# Adafruit_ESP32-S3_Reverse_TFT.net
KiCad netlist of a schematic drawn in EAGLE
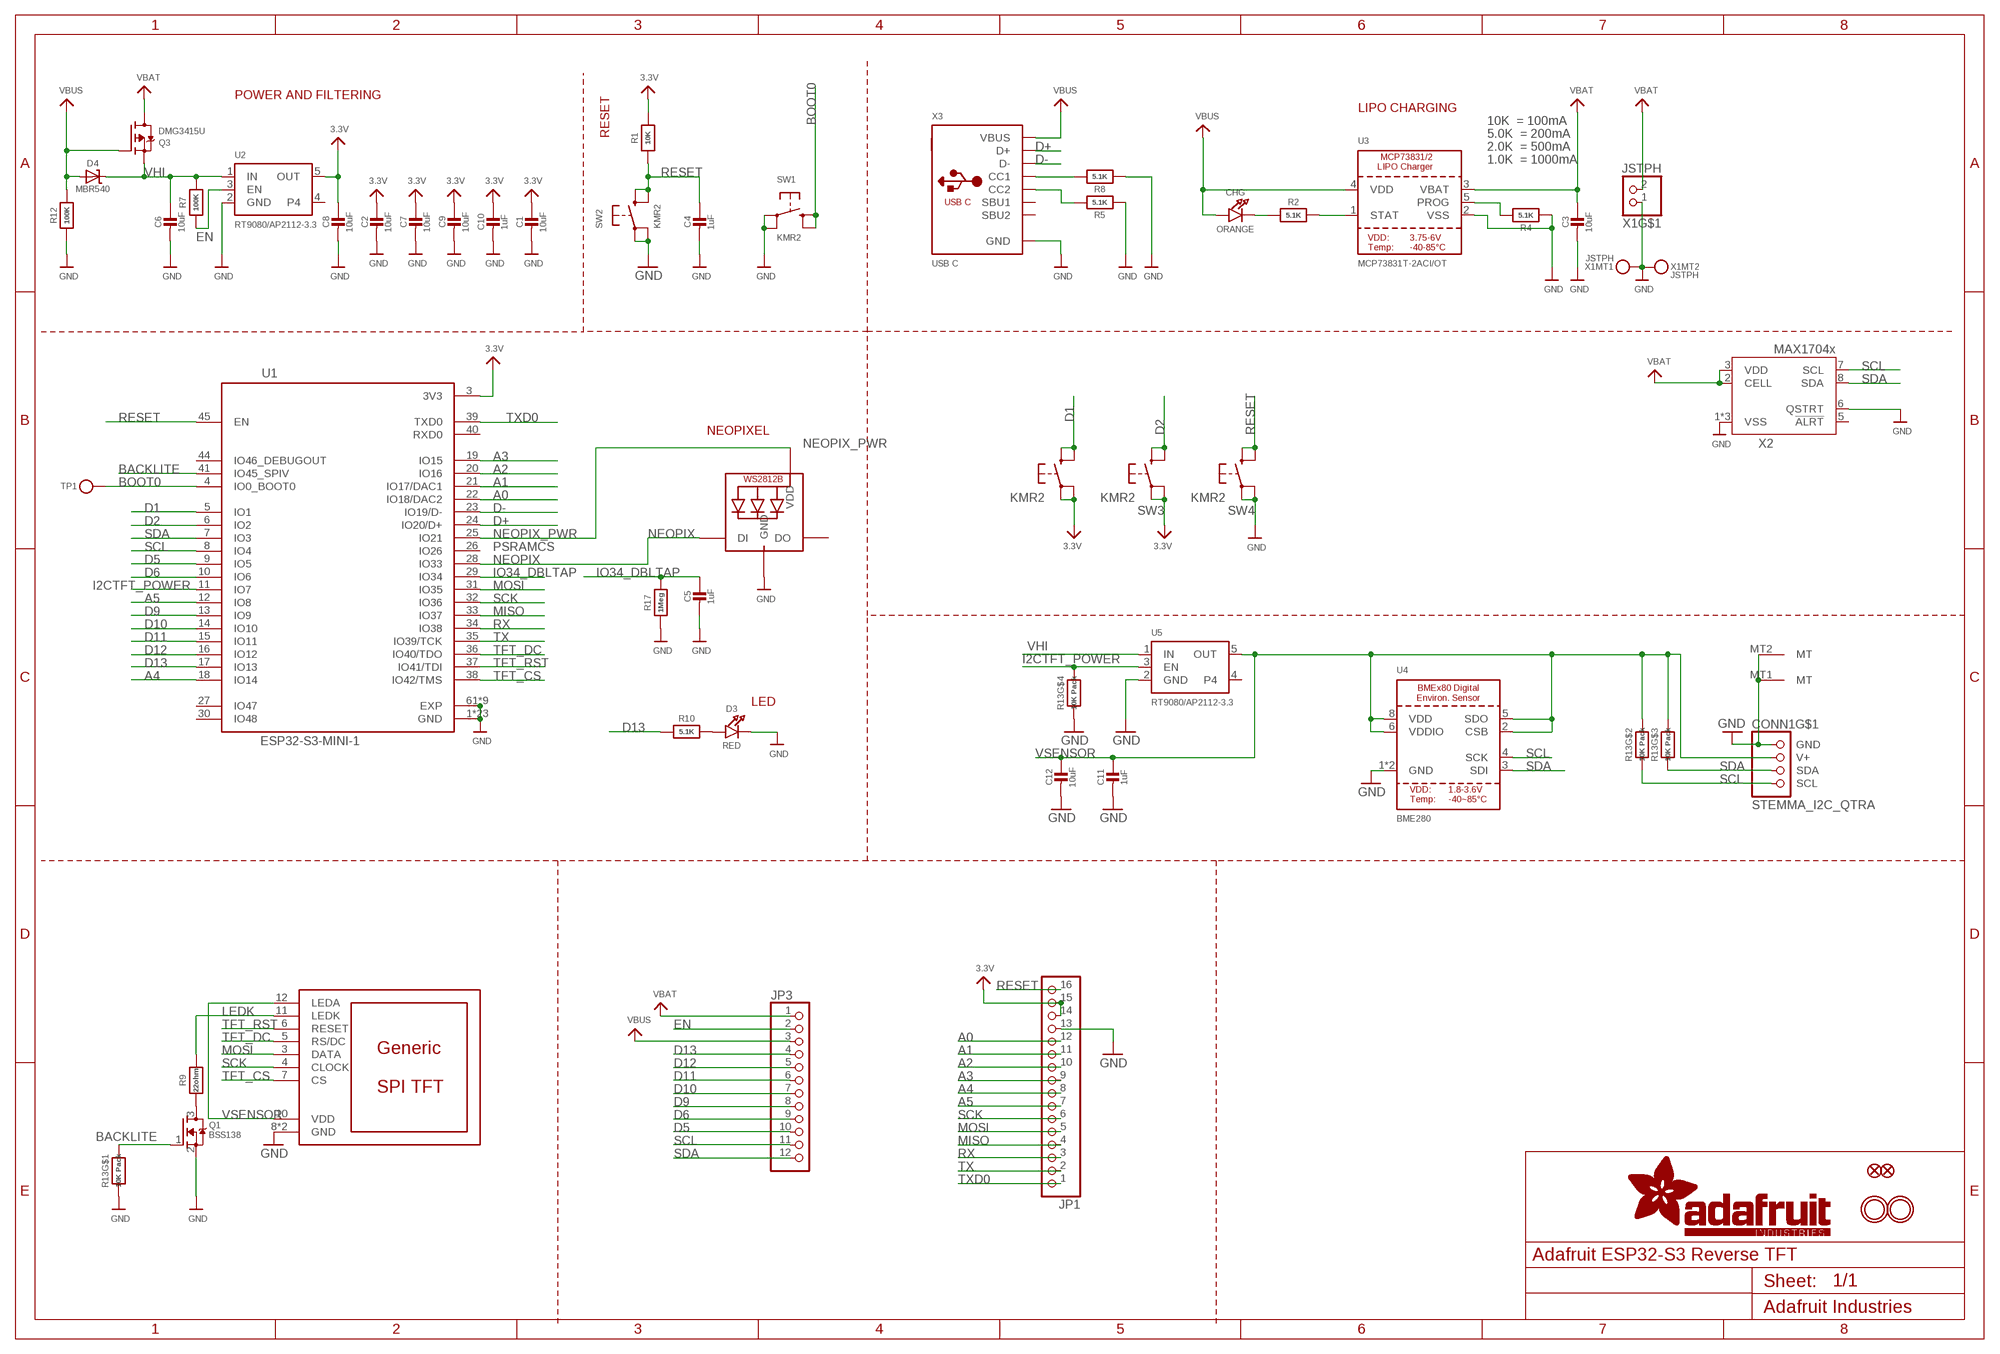
[diagram p0: schematic, sheet 1]

(export (version "E")
  (design (tool "Eeschema 10.0.6"))
  (components
    (comp (ref "C1")
      (value "10uF")
      (footprint "eagle-import:0805-NO")
      (libsource (lib "eagle-import") (part "CAP_CERAMIC0805-NOOUTLINE"))
    )
    (comp (ref "C2")
      (value "10uF")
      (footprint "eagle-import:0805-NO")
      (libsource (lib "eagle-import") (part "CAP_CERAMIC0805-NOOUTLINE"))
    )
    (comp (ref "C3")
      (value "10uF")
      (footprint "eagle-import:0805-NO")
      (libsource (lib "eagle-import") (part "CAP_CERAMIC0805-NOOUTLINE"))
    )
    (comp (ref "C4")
      (value "1uF")
      (footprint "eagle-import:0603-NO")
      (libsource (lib "eagle-import") (part "CAP_CERAMIC0603_NO"))
    )
    (comp (ref "C5")
      (value "1uF")
      (footprint "eagle-import:0603-NO")
      (libsource (lib "eagle-import") (part "CAP_CERAMIC0603_NO"))
    )
    (comp (ref "C6")
      (value "10uF")
      (footprint "eagle-import:0805-NO")
      (libsource (lib "eagle-import") (part "CAP_CERAMIC0805-NOOUTLINE"))
    )
    (comp (ref "C7")
      (value "10uF")
      (footprint "eagle-import:0805-NO")
      (libsource (lib "eagle-import") (part "CAP_CERAMIC0805-NOOUTLINE"))
    )
    (comp (ref "C8")
      (value "10uF")
      (footprint "eagle-import:0805-NO")
      (libsource (lib "eagle-import") (part "CAP_CERAMIC0805-NOOUTLINE"))
    )
    (comp (ref "C9")
      (value "10uF")
      (footprint "eagle-import:0805-NO")
      (libsource (lib "eagle-import") (part "CAP_CERAMIC0805-NOOUTLINE"))
    )
    (comp (ref "C10")
      (value "1uF")
      (footprint "eagle-import:0603-NO")
      (libsource (lib "eagle-import") (part "CAP_CERAMIC0603_NO"))
    )
    (comp (ref "C11")
      (value "1uF")
      (footprint "eagle-import:0603-NO")
      (libsource (lib "eagle-import") (part "CAP_CERAMIC0603_NO"))
    )
    (comp (ref "C12")
      (value "10uF")
      (footprint "eagle-import:0805-NO")
      (libsource (lib "eagle-import") (part "CAP_CERAMIC0805-NOOUTLINE"))
    )
    (comp (ref "CHG")
      (value "ORANGE")
      (footprint "eagle-import:CHIPLED_0603_NOOUTLINE")
      (libsource (lib "eagle-import") (part "LED0603_NOOUTLINE"))
    )
    (comp (ref "CONN1")
      (value "STEMMA_I2C_QTRA")
      (footprint "eagle-import:JST_SH4_RA")
      (libsource (lib "eagle-import") (part "STEMMA_I2C_QTRA"))
    )
    (comp (ref "D3")
      (value "RED")
      (footprint "eagle-import:CHIPLED_0603_NOOUTLINE")
      (libsource (lib "eagle-import") (part "LED0603_NOOUTLINE"))
    )
    (comp (ref "D4")
      (value "MBR540")
      (footprint "eagle-import:SOD-123")
      (libsource (lib "eagle-import") (part "DIODE-SCHOTTKYSOD-123"))
    )
    (comp (ref "DISP1")
      (value "DISP_LCD_GENERIC_SPI_1.14IN_240X135_WRAPUNDER")
      (footprint "eagle-import:TFT_1.14IN_240X135_WRAPUNDER")
      (libsource (lib "eagle-import") (part "DISP_LCD_GENERIC_SPI_1.14IN_240X135_WRAPUNDER"))
    )
    (comp (ref "JP1")
      (value "HEADER-1X16_MIN")
      (footprint "eagle-import:1X16_ROUND_MIN")
      (libsource (lib "eagle-import") (part "HEADER-1X16_MIN"))
    )
    (comp (ref "JP3")
      (value "HEADER-1X12_MIN")
      (footprint "eagle-import:1X12_ROUND_MIN")
      (libsource (lib "eagle-import") (part "HEADER-1X12_MIN"))
    )
    (comp (ref "LED1")
      (value "WS2812B_SK6805_1515")
      (footprint "eagle-import:SK6805_1515")
      (libsource (lib "eagle-import") (part "WS2812B_SK6805_1515"))
    )
    (comp (ref "Q1")
      (value "BSS138")
      (footprint "eagle-import:SC70")
      (libsource (lib "eagle-import") (part "MOSFET-N_SC70"))
    )
    (comp (ref "Q3")
      (value "DMG3415U")
      (footprint "eagle-import:SOT23-R")
      (libsource (lib "eagle-import") (part "MOSFET-P"))
    )
    (comp (ref "R1")
      (value "10K")
      (footprint "eagle-import:0603-NO")
      (libsource (lib "eagle-import") (part "RESISTOR_0603_NOOUT"))
    )
    (comp (ref "R2")
      (value "5.1K")
      (footprint "eagle-import:0603-NO")
      (libsource (lib "eagle-import") (part "RESISTOR_0603_NOOUT"))
    )
    (comp (ref "R4")
      (value "5.1K")
      (footprint "eagle-import:0603-NO")
      (libsource (lib "eagle-import") (part "RESISTOR_0603_NOOUT"))
    )
    (comp (ref "R5")
      (value "5.1K")
      (footprint "eagle-import:0603-NO")
      (libsource (lib "eagle-import") (part "RESISTOR_0603_NOOUT"))
    )
    (comp (ref "R7")
      (value "100K")
      (footprint "eagle-import:0603-NO")
      (libsource (lib "eagle-import") (part "RESISTOR_0603_NOOUT"))
    )
    (comp (ref "R8")
      (value "5.1K")
      (footprint "eagle-import:0603-NO")
      (libsource (lib "eagle-import") (part "RESISTOR_0603_NOOUT"))
    )
    (comp (ref "R9")
      (value "22ohm")
      (footprint "eagle-import:0603-NO")
      (libsource (lib "eagle-import") (part "RESISTOR_0603_NOOUT"))
    )
    (comp (ref "R10")
      (value "5.1K")
      (footprint "eagle-import:0603-NO")
      (libsource (lib "eagle-import") (part "RESISTOR_0603_NOOUT"))
    )
    (comp (ref "R12")
      (value "100K")
      (footprint "eagle-import:0603-NO")
      (libsource (lib "eagle-import") (part "RESISTOR_0603_NOOUT"))
    )
    (comp (ref "R13")
      (value "10K Pack")
      (footprint "eagle-import:RESPACK_4X0603")
      (libsource (lib "eagle-import") (part "RESISTOR_4PACK"))
    )
    (comp (ref "R17")
      (value "1Meg")
      (footprint "eagle-import:0603-NO")
      (libsource (lib "eagle-import") (part "RESISTOR_0603_NOOUT"))
    )
    (comp (ref "SW1")
      (value "KMR2")
      (footprint "eagle-import:BTN_RKB2_4.6X2.8")
      (libsource (lib "eagle-import") (part "SWITCH_TACT_SMT_RKB2"))
    )
    (comp (ref "SW2")
      (value "KMR2")
      (footprint "eagle-import:BTN_RKB2_4.6X2.8")
      (libsource (lib "eagle-import") (part "SWITCH_TACT_SMT_RKB2"))
    )
    (comp (ref "SW3")
      (value "KMR2")
      (footprint "eagle-import:BTN_RKB2_4.6X2.8")
      (libsource (lib "eagle-import") (part "SWITCH_TACT_SMT_RKB2"))
    )
    (comp (ref "SW4")
      (value "KMR2")
      (footprint "eagle-import:BTN_RKB2_4.6X2.8")
      (libsource (lib "eagle-import") (part "SWITCH_TACT_SMT_RKB2"))
    )
    (comp (ref "SW5")
      (value "KMR2")
      (footprint "eagle-import:BTN_RKB2_4.6X2.8")
      (libsource (lib "eagle-import") (part "SWITCH_TACT_SMT_RKB2"))
    )
    (comp (ref "TP1")
      (value "TESTPOINTROUND1.5MMNO")
      (footprint "eagle-import:TESTPOINT_ROUND_1.5MM_NO")
      (libsource (lib "eagle-import") (part "TESTPOINTROUND1.5MMNO"))
    )
    (comp (ref "U$31")
      (value "MOUNTINGHOLE2.5")
      (footprint "eagle-import:MOUNTINGHOLE_2.5_PLATED")
      (libsource (lib "eagle-import") (part "MOUNTINGHOLE2.5"))
    )
    (comp (ref "U$32")
      (value "MOUNTINGHOLE2.5")
      (footprint "eagle-import:MOUNTINGHOLE_2.5_PLATED")
      (libsource (lib "eagle-import") (part "MOUNTINGHOLE2.5"))
    )
    (comp (ref "U$34")
      (value "FIDUCIAL_1MM")
      (footprint "eagle-import:FIDUCIAL_1MM")
      (libsource (lib "eagle-import") (part "FIDUCIAL_1MM"))
    )
    (comp (ref "U$35")
      (value "FIDUCIAL_1MM")
      (footprint "eagle-import:FIDUCIAL_1MM")
      (libsource (lib "eagle-import") (part "FIDUCIAL_1MM"))
    )
    (comp (ref "U1")
      (value "ESP32-S3-MINI-1")
      (footprint "eagle-import:ESP32-S2-MINI-1")
      (fields
        (field (name "MANUFACTURER_PART_NUMBER") "ESP32-S2-MINI-1")
        (field (name "COPYRIGHT") "Copyright (C) 2018 Accelerated Designs. All rights reserved")
      )
      (libsource (lib "eagle-import") (part "ESP32-S3-MINI-1"))
    )
    (comp (ref "U2")
      (value "RT9080/AP2112-3.3")
      (footprint "eagle-import:SOT23-5")
      (fields (field (name "JLC_ROTATION") "0"))
      (libsource (lib "eagle-import") (part "VREG_SOT23-5"))
    )
    (comp (ref "U3")
      (value "MCP73831T-2ACI/OT")
      (footprint "eagle-import:SOT23-5")
      (libsource (lib "eagle-import") (part "MCP73831/2"))
    )
    (comp (ref "U4")
      (value "BME280")
      (footprint "eagle-import:BME280")
      (libsource (lib "eagle-import") (part "BME280"))
    )
    (comp (ref "U5")
      (value "RT9080/AP2112-3.3")
      (footprint "eagle-import:SOT23-5")
      (fields (field (name "JLC_ROTATION") "0"))
      (libsource (lib "eagle-import") (part "VREG_SOT23-5"))
    )
    (comp (ref "X1")
      (value "JSTPH")
      (footprint "eagle-import:JSTPH2_BATT")
      (libsource (lib "eagle-import") (part "CON_JST_PH_2PIN_MT_BATT"))
    )
    (comp (ref "X2")
      (value "MAX17048/T")
      (footprint "eagle-import:TDFN8_2X2MM")
      (libsource (lib "eagle-import") (part "MAX17048/T"))
    )
    (comp (ref "X3")
      (value "USB C")
      (footprint "eagle-import:USB_C_CUSB31-CFM2AX-01-X")
      (libsource (lib "eagle-import") (part "USB_C"))
    )
  )
  (nets
    (net (code "1") (name "/A0") (class "Default")
      (node (ref "JP1") (pin "12") (pinfunction "12_12") (pintype "passive"))
      (node (ref "U1") (pin "22") (pinfunction "IO18/DAC2_22") (pintype "bidirectional"))
    )
    (net (code "2") (name "/A1") (class "Default")
      (node (ref "JP1") (pin "11") (pinfunction "11_11") (pintype "passive"))
      (node (ref "U1") (pin "21") (pinfunction "IO17/DAC1_21") (pintype "bidirectional"))
    )
    (net (code "3") (name "/A2") (class "Default")
      (node (ref "JP1") (pin "10") (pinfunction "10_10") (pintype "passive"))
      (node (ref "U1") (pin "20") (pinfunction "IO16_20") (pintype "bidirectional"))
    )
    (net (code "4") (name "/A3") (class "Default")
      (node (ref "JP1") (pin "9") (pinfunction "9_9") (pintype "passive"))
      (node (ref "U1") (pin "19") (pinfunction "IO15_19") (pintype "bidirectional"))
    )
    (net (code "5") (name "/A4") (class "Default")
      (node (ref "JP1") (pin "8") (pinfunction "8_8") (pintype "passive"))
      (node (ref "U1") (pin "18") (pinfunction "IO14_18") (pintype "bidirectional"))
    )
    (net (code "6") (name "/A5") (class "Default")
      (node (ref "JP1") (pin "7") (pinfunction "7_7") (pintype "passive"))
      (node (ref "U1") (pin "12") (pinfunction "IO8_12") (pintype "bidirectional"))
    )
    (net (code "7") (name "/BACKLITE") (class "Default")
      (node (ref "Q1") (pin "1") (pinfunction "G_1") (pintype "bidirectional"))
      (node (ref "R13") (pin "8") (pinfunction "2_8") (pintype "passive"))
      (node (ref "U1") (pin "41") (pinfunction "IO45_SPIV_41") (pintype "bidirectional"))
    )
    (net (code "8") (name "/BOOT0") (class "Default")
      (node (ref "SW1") (pin "B") (pinfunction "S_B") (pintype "passive"))
      (node (ref "SW1") (pin "B'") (pinfunction "S1_B'") (pintype "passive"))
      (node (ref "TP1") (pin "P$1") (pinfunction "P$1_P$1") (pintype "bidirectional"))
      (node (ref "U1") (pin "4") (pinfunction "IO0_BOOT0_4") (pintype "bidirectional"))
    )
    (net (code "9") (name "/D+") (class "Default")
      (node (ref "U1") (pin "24") (pinfunction "IO20/D+_24") (pintype "bidirectional"))
      (node (ref "X3") (pin "A6") (pinfunction "D+_A6") (pintype "bidirectional"))
      (node (ref "X3") (pin "B6") (pinfunction "D+_B6") (pintype "bidirectional"))
    )
    (net (code "10") (name "/D-") (class "Default")
      (node (ref "U1") (pin "23") (pinfunction "IO19/D-_23") (pintype "bidirectional"))
      (node (ref "X3") (pin "A7") (pinfunction "D-_A7") (pintype "bidirectional"))
      (node (ref "X3") (pin "B7") (pinfunction "D-_B7") (pintype "bidirectional"))
    )
    (net (code "11") (name "/D1") (class "Default")
      (node (ref "SW5") (pin "B") (pinfunction "S_B") (pintype "passive"))
      (node (ref "SW5") (pin "B'") (pinfunction "S1_B'") (pintype "passive"))
      (node (ref "U1") (pin "5") (pinfunction "IO1_5") (pintype "bidirectional"))
    )
    (net (code "12") (name "/D2") (class "Default")
      (node (ref "SW3") (pin "B") (pinfunction "S_B") (pintype "passive"))
      (node (ref "SW3") (pin "B'") (pinfunction "S1_B'") (pintype "passive"))
      (node (ref "U1") (pin "6") (pinfunction "IO2_6") (pintype "bidirectional"))
    )
    (net (code "13") (name "/D5") (class "Default")
      (node (ref "JP3") (pin "10") (pinfunction "10_10") (pintype "passive"))
      (node (ref "U1") (pin "9") (pinfunction "IO5_9") (pintype "bidirectional"))
    )
    (net (code "14") (name "/D6") (class "Default")
      (node (ref "JP3") (pin "9") (pinfunction "9_9") (pintype "passive"))
      (node (ref "U1") (pin "10") (pinfunction "IO6_10") (pintype "bidirectional"))
    )
    (net (code "15") (name "/D9") (class "Default")
      (node (ref "JP3") (pin "8") (pinfunction "8_8") (pintype "passive"))
      (node (ref "U1") (pin "13") (pinfunction "IO9_13") (pintype "bidirectional"))
    )
    (net (code "16") (name "/D10") (class "Default")
      (node (ref "JP3") (pin "7") (pinfunction "7_7") (pintype "passive"))
      (node (ref "U1") (pin "14") (pinfunction "IO10_14") (pintype "bidirectional"))
    )
    (net (code "17") (name "/D11") (class "Default")
      (node (ref "JP3") (pin "6") (pinfunction "6_6") (pintype "passive"))
      (node (ref "U1") (pin "15") (pinfunction "IO11_15") (pintype "bidirectional"))
    )
    (net (code "18") (name "/D12") (class "Default")
      (node (ref "JP3") (pin "5") (pinfunction "5_5") (pintype "passive"))
      (node (ref "U1") (pin "16") (pinfunction "IO12_16") (pintype "bidirectional"))
    )
    (net (code "19") (name "/D13") (class "Default")
      (node (ref "JP3") (pin "4") (pinfunction "4_4") (pintype "passive"))
      (node (ref "R10") (pin "1") (pinfunction "1_1") (pintype "passive"))
      (node (ref "U1") (pin "17") (pinfunction "IO13_17") (pintype "bidirectional"))
    )
    (net (code "20") (name "/EN") (class "Default")
      (node (ref "JP3") (pin "2") (pinfunction "2_2") (pintype "passive"))
      (node (ref "R7") (pin "1") (pinfunction "1_1") (pintype "passive"))
      (node (ref "U2") (pin "3") (pinfunction "EN_3") (pintype "input"))
    )
    (net (code "21") (name "/I2CTFT_POWER") (class "Default")
      (node (ref "R13") (pin "5") (pinfunction "2_5") (pintype "passive"))
      (node (ref "U1") (pin "11") (pinfunction "IO7_11") (pintype "bidirectional"))
      (node (ref "U5") (pin "3") (pinfunction "EN_3") (pintype "input"))
    )
    (net (code "22") (name "/IO34_DBLTAP") (class "Default")
      (node (ref "C5") (pin "1") (pinfunction "1_1") (pintype "passive"))
      (node (ref "R17") (pin "2") (pinfunction "2_2") (pintype "passive"))
      (node (ref "U1") (pin "29") (pinfunction "IO34_29") (pintype "input"))
    )
    (net (code "23") (name "/LEDK") (class "Default")
      (node (ref "DISP1") (pin "11") (pinfunction "LEDK_11") (pintype "input"))
      (node (ref "R9") (pin "2") (pinfunction "2_2") (pintype "passive"))
    )
    (net (code "24") (name "/MISO") (class "Default")
      (node (ref "JP1") (pin "4") (pinfunction "4_4") (pintype "passive"))
      (node (ref "U1") (pin "33") (pinfunction "IO37_33") (pintype "bidirectional"))
    )
    (net (code "25") (name "/MOSI") (class "Default")
      (node (ref "DISP1") (pin "3") (pinfunction "DATA_3") (pintype "bidirectional"))
      (node (ref "JP1") (pin "5") (pinfunction "5_5") (pintype "passive"))
      (node (ref "U1") (pin "31") (pinfunction "IO35_31") (pintype "input"))
    )
    (net (code "26") (name "/NEOPIX") (class "Default")
      (node (ref "LED1") (pin "1") (pinfunction "DI_1") (pintype "input"))
      (node (ref "U1") (pin "28") (pinfunction "IO33_28") (pintype "bidirectional"))
    )
    (net (code "27") (name "/NEOPIX_PWR") (class "Default")
      (node (ref "LED1") (pin "2") (pinfunction "VDD_2") (pintype "power_in"))
      (node (ref "U1") (pin "25") (pinfunction "IO21_25") (pintype "bidirectional"))
    )
    (net (code "28") (name "/RESET") (class "Default")
      (node (ref "C4") (pin "1") (pinfunction "1_1") (pintype "passive"))
      (node (ref "JP1") (pin "16") (pinfunction "16_16") (pintype "passive"))
      (node (ref "R1") (pin "1") (pinfunction "1_1") (pintype "passive"))
      (node (ref "SW2") (pin "B") (pinfunction "S_B") (pintype "passive"))
      (node (ref "SW2") (pin "B'") (pinfunction "S1_B'") (pintype "passive"))
      (node (ref "SW4") (pin "B") (pinfunction "S_B") (pintype "passive"))
      (node (ref "SW4") (pin "B'") (pinfunction "S1_B'") (pintype "passive"))
      (node (ref "U1") (pin "45") (pinfunction "EN_45") (pintype "input"))
    )
    (net (code "29") (name "/RX") (class "Default")
      (node (ref "JP1") (pin "3") (pinfunction "3_3") (pintype "passive"))
      (node (ref "U1") (pin "34") (pinfunction "IO38_34") (pintype "bidirectional"))
    )
    (net (code "30") (name "/SCK") (class "Default")
      (node (ref "DISP1") (pin "4") (pinfunction "CLOCK_4") (pintype "input"))
      (node (ref "JP1") (pin "6") (pinfunction "6_6") (pintype "passive"))
      (node (ref "U1") (pin "32") (pinfunction "IO36_32") (pintype "bidirectional"))
    )
    (net (code "31") (name "/SCL") (class "Default")
      (node (ref "CONN1") (pin "4") (pinfunction "SCL_4") (pintype "passive"))
      (node (ref "JP3") (pin "11") (pinfunction "11_11") (pintype "passive"))
      (node (ref "R13") (pin "2") (pinfunction "1_2") (pintype "passive"))
      (node (ref "U1") (pin "8") (pinfunction "IO4_8") (pintype "bidirectional"))
      (node (ref "U4") (pin "4") (pinfunction "SCK_4") (pintype "input"))
      (node (ref "X2") (pin "7") (pinfunction "SCL_7") (pintype "bidirectional"))
    )
    (net (code "32") (name "/SDA") (class "Default")
      (node (ref "CONN1") (pin "3") (pinfunction "SDA_3") (pintype "passive"))
      (node (ref "JP3") (pin "12") (pinfunction "12_12") (pintype "passive"))
      (node (ref "R13") (pin "3") (pinfunction "1_3") (pintype "passive"))
      (node (ref "U1") (pin "7") (pinfunction "IO3_7") (pintype "bidirectional"))
      (node (ref "U4") (pin "3") (pinfunction "SDI_3") (pintype "input"))
      (node (ref "X2") (pin "8") (pinfunction "SDA_8") (pintype "bidirectional"))
    )
    (net (code "33") (name "/TFT_CS") (class "Default")
      (node (ref "DISP1") (pin "7") (pinfunction "CS_7") (pintype "input"))
      (node (ref "U1") (pin "38") (pinfunction "IO42/TMS_38") (pintype "bidirectional"))
    )
    (net (code "34") (name "/TFT_DC") (class "Default")
      (node (ref "DISP1") (pin "5") (pinfunction "RS/DC_5") (pintype "input"))
      (node (ref "U1") (pin "36") (pinfunction "IO40/TDO_36") (pintype "bidirectional"))
    )
    (net (code "35") (name "/TFT_RST") (class "Default")
      (node (ref "DISP1") (pin "6") (pinfunction "RESET_6") (pintype "input"))
      (node (ref "U1") (pin "37") (pinfunction "IO41/TDI_37") (pintype "bidirectional"))
    )
    (net (code "36") (name "/TX") (class "Default")
      (node (ref "JP1") (pin "2") (pinfunction "2_2") (pintype "passive"))
      (node (ref "U1") (pin "35") (pinfunction "IO39/TCK_35") (pintype "bidirectional"))
    )
    (net (code "37") (name "/TXD0") (class "Default")
      (node (ref "JP1") (pin "1") (pinfunction "1_1") (pintype "passive"))
      (node (ref "U1") (pin "39") (pinfunction "TXD0_39") (pintype "bidirectional"))
    )
    (net (code "38") (name "/VHI") (class "Default")
      (node (ref "C6") (pin "1") (pinfunction "1_1") (pintype "passive"))
      (node (ref "D4") (pin "C") (pinfunction "C_C") (pintype "passive"))
      (node (ref "Q3") (pin "2") (pinfunction "S_2") (pintype "passive"))
      (node (ref "R7") (pin "2") (pinfunction "2_2") (pintype "passive"))
      (node (ref "U2") (pin "1") (pinfunction "IN_1") (pintype "power_in"))
      (node (ref "U5") (pin "1") (pinfunction "IN_1") (pintype "power_in"))
    )
    (net (code "39") (name "/VSENSOR") (class "Default")
      (node (ref "C11") (pin "1") (pinfunction "1_1") (pintype "passive"))
      (node (ref "C12") (pin "1") (pinfunction "1_1") (pintype "passive"))
      (node (ref "CONN1") (pin "2") (pinfunction "V+_2") (pintype "passive"))
      (node (ref "DISP1") (pin "10") (pinfunction "VDD_10") (pintype "power_in"))
      (node (ref "DISP1") (pin "12") (pinfunction "LEDA_12") (pintype "input"))
      (node (ref "R13") (pin "6") (pinfunction "2_6") (pintype "passive"))
      (node (ref "R13") (pin "7") (pinfunction "2_7") (pintype "passive"))
      (node (ref "U4") (pin "2") (pinfunction "CSB_2") (pintype "input"))
      (node (ref "U4") (pin "5") (pinfunction "SDO_5") (pintype "output"))
      (node (ref "U4") (pin "6") (pinfunction "VDDIO_6") (pintype "power_in"))
      (node (ref "U4") (pin "8") (pinfunction "VDD_8") (pintype "power_in"))
      (node (ref "U5") (pin "5") (pinfunction "OUT_5") (pintype "power_in"))
    )
    (net (code "40") (name "3.3V") (class "Default")
      (node (ref "C1") (pin "1") (pinfunction "1_1") (pintype "passive"))
      (node (ref "C10") (pin "1") (pinfunction "1_1") (pintype "passive"))
      (node (ref "C2") (pin "1") (pinfunction "1_1") (pintype "passive"))
      (node (ref "C7") (pin "1") (pinfunction "1_1") (pintype "passive"))
      (node (ref "C8") (pin "1") (pinfunction "1_1") (pintype "passive"))
      (node (ref "C9") (pin "1") (pinfunction "1_1") (pintype "passive"))
      (node (ref "JP1") (pin "14") (pinfunction "14_14") (pintype "passive"))
      (node (ref "JP1") (pin "15") (pinfunction "15_15") (pintype "passive"))
      (node (ref "R1") (pin "2") (pinfunction "2_2") (pintype "passive"))
      (node (ref "SW3") (pin "A") (pinfunction "P_A") (pintype "passive"))
      (node (ref "SW3") (pin "A'") (pinfunction "P1_A'") (pintype "passive"))
      (node (ref "SW5") (pin "A") (pinfunction "P_A") (pintype "passive"))
      (node (ref "SW5") (pin "A'") (pinfunction "P1_A'") (pintype "passive"))
      (node (ref "U1") (pin "3") (pinfunction "3V3_3") (pintype "power_in"))
      (node (ref "U2") (pin "5") (pinfunction "OUT_5") (pintype "power_in"))
    )
    (net (code "41") (name "GND") (class "Default")
      (node (ref "C1") (pin "2") (pinfunction "2_2") (pintype "passive"))
      (node (ref "C10") (pin "2") (pinfunction "2_2") (pintype "passive"))
      (node (ref "C11") (pin "2") (pinfunction "2_2") (pintype "passive"))
      (node (ref "C12") (pin "2") (pinfunction "2_2") (pintype "passive"))
      (node (ref "C2") (pin "2") (pinfunction "2_2") (pintype "passive"))
      (node (ref "C3") (pin "2") (pinfunction "2_2") (pintype "passive"))
      (node (ref "C4") (pin "2") (pinfunction "2_2") (pintype "passive"))
      (node (ref "C5") (pin "2") (pinfunction "2_2") (pintype "passive"))
      (node (ref "C6") (pin "2") (pinfunction "2_2") (pintype "passive"))
      (node (ref "C7") (pin "2") (pinfunction "2_2") (pintype "passive"))
      (node (ref "C8") (pin "2") (pinfunction "2_2") (pintype "passive"))
      (node (ref "C9") (pin "2") (pinfunction "2_2") (pintype "passive"))
      (node (ref "CONN1") (pin "1") (pinfunction "GND_1") (pintype "passive"))
      (node (ref "CONN1") (pin "MT1") (pinfunction "MT_MT1") (pintype "bidirectional"))
      (node (ref "CONN1") (pin "MT2") (pinfunction "MT_MT2") (pintype "bidirectional"))
      (node (ref "D3") (pin "C") (pinfunction "C_C") (pintype "passive"))
      (node (ref "DISP1") (pin "13") (pinfunction "GND_13") (pintype "power_in"))
      (node (ref "DISP1") (pin "8") (pinfunction "GND_8") (pintype "power_in"))
      (node (ref "JP1") (pin "13") (pinfunction "13_13") (pintype "passive"))
      (node (ref "LED1") (pin "4") (pinfunction "GND_4") (pintype "power_in"))
      (node (ref "Q1") (pin "2") (pinfunction "S_2") (pintype "bidirectional"))
      (node (ref "R12") (pin "1") (pinfunction "1_1") (pintype "passive"))
      (node (ref "R13") (pin "1") (pinfunction "1_1") (pintype "passive"))
      (node (ref "R13") (pin "4") (pinfunction "1_4") (pintype "passive"))
      (node (ref "R17") (pin "1") (pinfunction "1_1") (pintype "passive"))
      (node (ref "R4") (pin "1") (pinfunction "1_1") (pintype "passive"))
      (node (ref "R5") (pin "1") (pinfunction "1_1") (pintype "passive"))
      (node (ref "R8") (pin "1") (pinfunction "1_1") (pintype "passive"))
      (node (ref "SW1") (pin "A") (pinfunction "P_A") (pintype "passive"))
      (node (ref "SW1") (pin "A'") (pinfunction "P1_A'") (pintype "passive"))
      (node (ref "SW2") (pin "A") (pinfunction "P_A") (pintype "passive"))
      (node (ref "SW2") (pin "A'") (pinfunction "P1_A'") (pintype "passive"))
      (node (ref "SW4") (pin "A") (pinfunction "P_A") (pintype "passive"))
      (node (ref "SW4") (pin "A'") (pinfunction "P1_A'") (pintype "passive"))
      (node (ref "U1") (pin "1") (pinfunction "GND_1") (pintype "power_in"))
      (node (ref "U1") (pin "2") (pinfunction "GND_2") (pintype "power_in"))
      (node (ref "U1") (pin "42") (pinfunction "GND_42") (pintype "power_in"))
      (node (ref "U1") (pin "43") (pinfunction "GND_43") (pintype "power_in"))
      (node (ref "U1") (pin "46") (pinfunction "GND_46") (pintype "power_in"))
      (node (ref "U1") (pin "47") (pinfunction "GND_47") (pintype "power_in"))
      (node (ref "U1") (pin "48") (pinfunction "GND_48") (pintype "power_in"))
      (node (ref "U1") (pin "49") (pinfunction "GND_49") (pintype "power_in"))
      (node (ref "U1") (pin "50") (pinfunction "GND_50") (pintype "power_in"))
      (node (ref "U1") (pin "51") (pinfunction "GND_51") (pintype "power_in"))
      (node (ref "U1") (pin "52") (pinfunction "GND_52") (pintype "power_in"))
      (node (ref "U1") (pin "53") (pinfunction "GND_53") (pintype "power_in"))
      (node (ref "U1") (pin "54") (pinfunction "GND_54") (pintype "power_in"))
      (node (ref "U1") (pin "55") (pinfunction "GND_55") (pintype "power_in"))
      (node (ref "U1") (pin "56") (pinfunction "GND_56") (pintype "power_in"))
      (node (ref "U1") (pin "57") (pinfunction "GND_57") (pintype "power_in"))
      (node (ref "U1") (pin "58") (pinfunction "GND_58") (pintype "power_in"))
      (node (ref "U1") (pin "59") (pinfunction "GND_59") (pintype "power_in"))
      (node (ref "U1") (pin "60") (pinfunction "GND_60") (pintype "power_in"))
      (node (ref "U1") (pin "61") (pinfunction "EXP_61") (pintype "power_in"))
      (node (ref "U1") (pin "62") (pinfunction "GND_62") (pintype "power_in"))
      (node (ref "U1") (pin "63") (pinfunction "GND_63") (pintype "power_in"))
      (node (ref "U1") (pin "64") (pinfunction "GND_64") (pintype "power_in"))
      (node (ref "U1") (pin "65") (pinfunction "GND_65") (pintype "power_in"))
      (node (ref "U1") (pin "66") (pinfunction "EXP_66") (pintype "power_in"))
      (node (ref "U1") (pin "67") (pinfunction "EXP_67") (pintype "power_in"))
      (node (ref "U1") (pin "68") (pinfunction "EXP_68") (pintype "power_in"))
      (node (ref "U1") (pin "69") (pinfunction "EXP_69") (pintype "power_in"))
      (node (ref "U1") (pin "70") (pinfunction "EXP_70") (pintype "power_in"))
      (node (ref "U1") (pin "71") (pinfunction "EXP_71") (pintype "power_in"))
      (node (ref "U1") (pin "72") (pinfunction "EXP_72") (pintype "power_in"))
      (node (ref "U1") (pin "73") (pinfunction "EXP_73") (pintype "power_in"))
      (node (ref "U2") (pin "2") (pinfunction "GND_2") (pintype "power_in"))
      (node (ref "U3") (pin "2") (pinfunction "VSS_2") (pintype "power_in"))
      (node (ref "U4") (pin "1") (pinfunction "GND_1") (pintype "power_in"))
      (node (ref "U4") (pin "7") (pinfunction "GND_7") (pintype "power_in"))
      (node (ref "U5") (pin "2") (pinfunction "GND_2") (pintype "power_in"))
      (node (ref "X1") (pin "1") (pinfunction "1_1") (pintype "passive"))
      (node (ref "X1") (pin "NC1") (pinfunction "P$1_NC1") (pintype "bidirectional"))
      (node (ref "X1") (pin "NC2") (pinfunction "P$1_NC2") (pintype "bidirectional"))
      (node (ref "X2") (pin "1") (pinfunction "VSS_1") (pintype "power_in"))
      (node (ref "X2") (pin "4") (pinfunction "VSS_4") (pintype "power_in"))
      (node (ref "X2") (pin "6") (pinfunction "QSTRT_6") (pintype "input"))
      (node (ref "X2") (pin "THERMAL") (pinfunction "VSS_THERMAL") (pintype "power_in"))
      (node (ref "X3") (pin "A1B12") (pinfunction "GND_A1B12") (pintype "power_in"))
      (node (ref "X3") (pin "B1A12") (pinfunction "GND_B1A12") (pintype "power_in"))
    )
    (net (code "42") (name "Net-(CHG-PadC)") (class "Default")
      (node (ref "CHG") (pin "C") (pinfunction "C_C") (pintype "passive"))
      (node (ref "R2") (pin "1") (pinfunction "1_1") (pintype "passive"))
    )
    (net (code "43") (name "Net-(D3-PadA)") (class "Default")
      (node (ref "D3") (pin "A") (pinfunction "A_A") (pintype "passive"))
      (node (ref "R10") (pin "2") (pinfunction "2_2") (pintype "passive"))
    )
    (net (code "44") (name "Net-(Q1-D)") (class "Default")
      (node (ref "Q1") (pin "3") (pinfunction "D_3") (pintype "bidirectional"))
      (node (ref "R9") (pin "1") (pinfunction "1_1") (pintype "passive"))
    )
    (net (code "45") (name "Net-(U3-PROG)") (class "Default")
      (node (ref "R4") (pin "2") (pinfunction "2_2") (pintype "passive"))
      (node (ref "U3") (pin "5") (pinfunction "PROG_5") (pintype "input"))
    )
    (net (code "46") (name "Net-(U3-STAT)") (class "Default")
      (node (ref "R2") (pin "2") (pinfunction "2_2") (pintype "passive"))
      (node (ref "U3") (pin "1") (pinfunction "STAT_1") (pintype "output"))
    )
    (net (code "47") (name "Net-(X3-CC1)") (class "Default")
      (node (ref "R8") (pin "2") (pinfunction "2_2") (pintype "passive"))
      (node (ref "X3") (pin "A5") (pinfunction "CC1_A5") (pintype "bidirectional"))
    )
    (net (code "48") (name "Net-(X3-CC2)") (class "Default")
      (node (ref "R5") (pin "2") (pinfunction "2_2") (pintype "passive"))
      (node (ref "X3") (pin "B5") (pinfunction "CC2_B5") (pintype "bidirectional"))
    )
    (net (code "49") (name "VBAT") (class "Default")
      (node (ref "C3") (pin "1") (pinfunction "1_1") (pintype "passive"))
      (node (ref "JP3") (pin "1") (pinfunction "1_1") (pintype "passive"))
      (node (ref "Q3") (pin "3") (pinfunction "D_3") (pintype "passive"))
      (node (ref "U3") (pin "3") (pinfunction "VBAT_3") (pintype "power_in"))
      (node (ref "X1") (pin "2") (pinfunction "2_2") (pintype "passive"))
      (node (ref "X2") (pin "2") (pinfunction "CELL_2") (pintype "power_in"))
      (node (ref "X2") (pin "3") (pinfunction "VDD_3") (pintype "power_in"))
    )
    (net (code "50") (name "VBUS") (class "Default")
      (node (ref "CHG") (pin "A") (pinfunction "A_A") (pintype "passive"))
      (node (ref "D4") (pin "A") (pinfunction "A_A") (pintype "passive"))
      (node (ref "JP3") (pin "3") (pinfunction "3_3") (pintype "passive"))
      (node (ref "Q3") (pin "1") (pinfunction "G_1") (pintype "passive"))
      (node (ref "R12") (pin "2") (pinfunction "2_2") (pintype "passive"))
      (node (ref "U3") (pin "4") (pinfunction "VDD_4") (pintype "power_in"))
      (node (ref "X3") (pin "A4B9") (pinfunction "VBUS_A4B9") (pintype "power_in"))
      (node (ref "X3") (pin "B4A9") (pinfunction "VBUS_B4A9") (pintype "power_in"))
    )
    (net (code "51") (name "unconnected-(LED1-DO-Pad3)") (class "Default")
      (node (ref "LED1") (pin "3") (pinfunction "DO_3") (pintype "output"))
    )
    (net (code "52") (name "unconnected-(U1-IO26-Pad26)") (class "Default")
      (node (ref "U1") (pin "26") (pinfunction "IO26_26") (pintype "bidirectional"))
    )
    (net (code "53") (name "unconnected-(U1-IO46_DEBUGOUT-Pad44)") (class "Default")
      (node (ref "U1") (pin "44") (pinfunction "IO46_DEBUGOUT_44") (pintype "input"))
    )
    (net (code "54") (name "unconnected-(U1-IO47-Pad27)") (class "Default")
      (node (ref "U1") (pin "27") (pinfunction "IO47_27") (pintype "bidirectional"))
    )
    (net (code "55") (name "unconnected-(U1-IO48-Pad30)") (class "Default")
      (node (ref "U1") (pin "30") (pinfunction "IO48_30") (pintype "bidirectional"))
    )
    (net (code "56") (name "unconnected-(U1-RXD0-Pad40)") (class "Default")
      (node (ref "U1") (pin "40") (pinfunction "RXD0_40") (pintype "bidirectional"))
    )
    (net (code "57") (name "unconnected-(U2-P4-Pad4)") (class "Default")
      (node (ref "U2") (pin "4") (pinfunction "P4_4") (pintype "bidirectional"))
    )
    (net (code "58") (name "unconnected-(U5-P4-Pad4)") (class "Default")
      (node (ref "U5") (pin "4") (pinfunction "P4_4") (pintype "bidirectional"))
    )
    (net (code "59") (name "unconnected-(X2-~{ALRT}-Pad5)") (class "Default")
      (node (ref "X2") (pin "5") (pinfunction "~{ALRT}_5") (pintype "output"))
    )
    (net (code "60") (name "unconnected-(X3-SBU1-PadA8)") (class "Default")
      (node (ref "X3") (pin "A8") (pinfunction "SBU1_A8") (pintype "bidirectional"))
    )
    (net (code "61") (name "unconnected-(X3-SBU2-PadB8)") (class "Default")
      (node (ref "X3") (pin "B8") (pinfunction "SBU2_B8") (pintype "bidirectional"))
    )
  )
)
